# MCU.net
KiCad netlist of a schematic drawn in Altium Designer
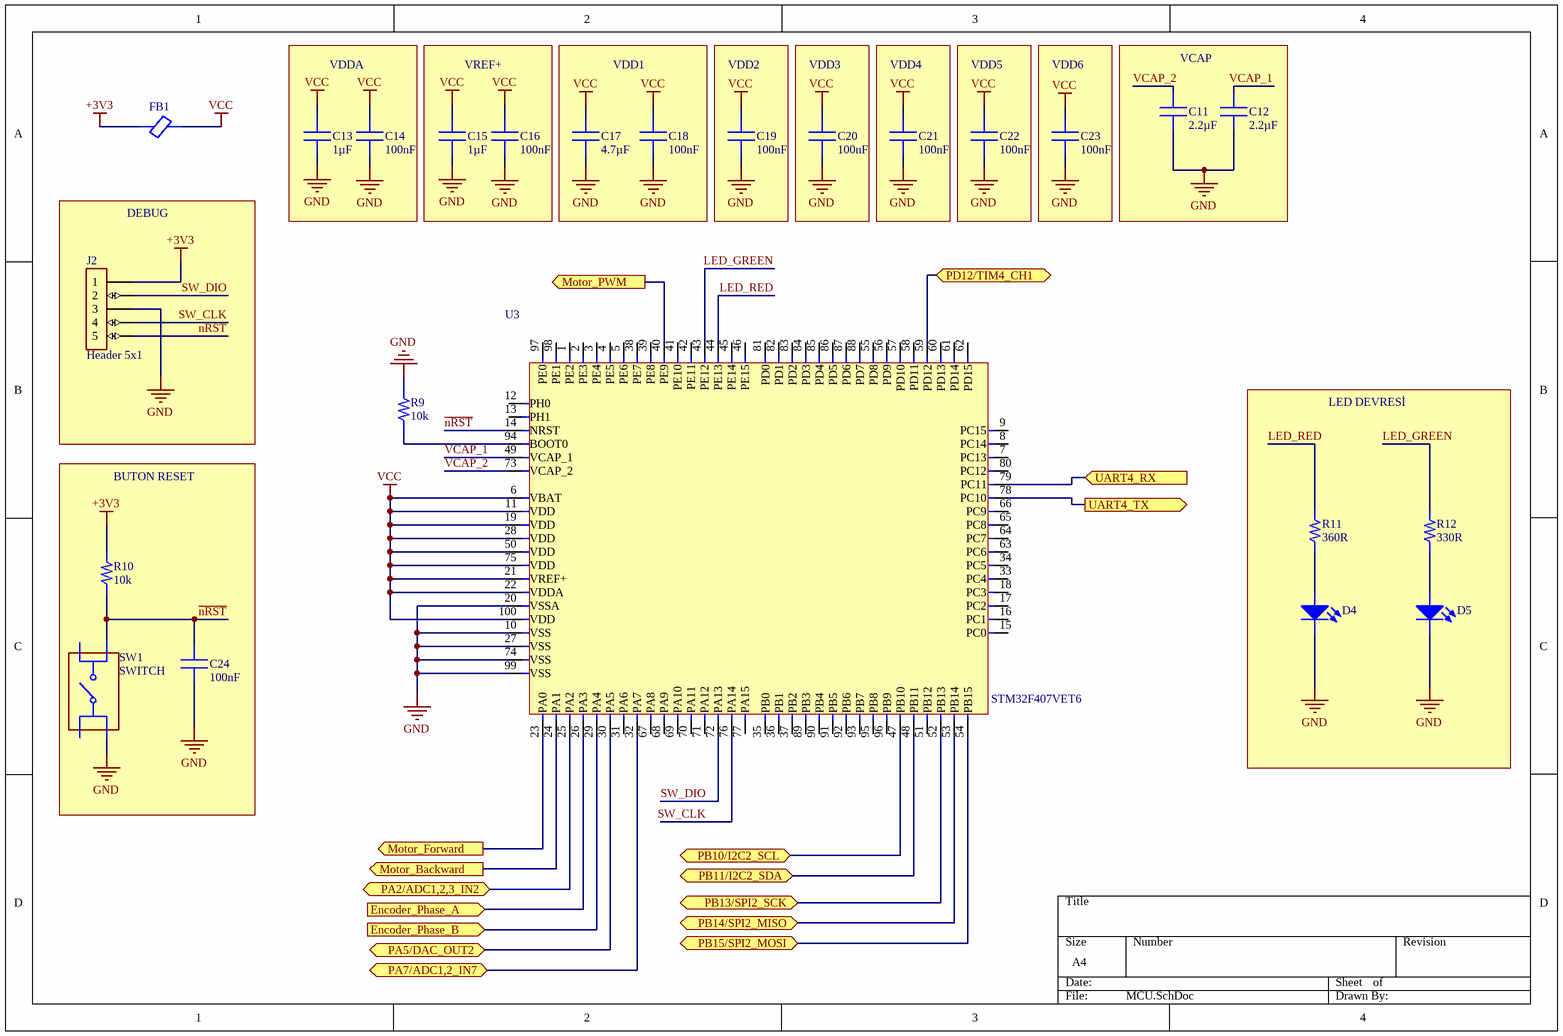
[diagram p0: MCU.SchDoc]

(export (version "E")
  (design (tool "Eeschema 10.0.6"))
  (components
    (comp (ref "C11")
      (value "2.2µF")
      (footprint "CAP 0402 2.2UF")
      (description "MLCC (1005) 0402 2.2uF 16VDC ±10% X5R CL05A225KO5NQNC")
      (fields (field (name "MANUFACTURER") "SAMSUNG") (field (name "TOLERANCE") "±10 %"))
      (libsource (lib "Motor Controller SchLib") (part "CAP 0402 2.2uF CL05A225KO5NQNC"))
    )
    (comp (ref "C12")
      (value "2.2µF")
      (footprint "CAP 0402 2.2UF")
      (description "MLCC (1005) 0402 2.2uF 16VDC ±10% X5R CL05A225KO5NQNC")
      (fields (field (name "MANUFACTURER") "SAMSUNG") (field (name "TOLERANCE") "±10 %"))
      (libsource (lib "Motor Controller SchLib") (part "CAP 0402 2.2uF CL05A225KO5NQNC"))
    )
    (comp (ref "C13")
      (value "1µF")
      (footprint "CAP 1uF 0402")
      (description "MLCC (1005) 0402 1uF 16VDC ±10% X5R CL05A105KO5NNNC")
      (fields (field (name "MANUFACTURER") "SAMSUNG") (field (name "TOLERANCE") "±10 %"))
      (libsource (lib "Motor Controller SchLib") (part "CAP 0402 1µF CL05A105KO5NNNC"))
    )
    (comp (ref "C14")
      (value "100nF")
      (footprint "CAP 100nF 0402")
      (description "MLCC (1005) 0402 100nF 16VDC ±10% X7R")
      (fields (field (name "TOLERANCE") "±10 %") (field (name "MANUFACTURER") "SAMSUNG"))
      (libsource (lib "Motor Controller SchLib") (part "CAP 0402 100nF"))
    )
    (comp (ref "C15")
      (value "1µF")
      (footprint "CAP 1uF 0402")
      (description "MLCC (1005) 0402 1uF 16VDC ±10% X5R CL05A105KO5NNNC")
      (fields (field (name "MANUFACTURER") "SAMSUNG") (field (name "TOLERANCE") "±10 %"))
      (libsource (lib "Motor Controller SchLib") (part "CAP 0402 1µF CL05A105KO5NNNC"))
    )
    (comp (ref "C16")
      (value "100nF")
      (footprint "CAP 100nF 0402")
      (description "MLCC (1005) 0402 100nF 16VDC ±10% X7R")
      (fields (field (name "TOLERANCE") "±10 %") (field (name "MANUFACTURER") "SAMSUNG"))
      (libsource (lib "Motor Controller SchLib") (part "CAP 0402 100nF"))
    )
    (comp (ref "C17")
      (value "4.7µF")
      (footprint "CAP 0402 4.7uF")
      (description "MLCC (1005) 0402 4.7uF 16VDC ±20% X5R CL05A475MO5LUNC")
      (fields (field (name "MANUFACTURER") "SAMSUNG") (field (name "TOLERANCE") "±20 %"))
      (libsource (lib "Motor Controller SchLib") (part "CAP 0402 4.7uF CL05A475MO5LUNC"))
    )
    (comp (ref "C18")
      (value "100nF")
      (footprint "CAP 100nF 0402")
      (description "MLCC (1005) 0402 100nF 16VDC ±10% X7R")
      (fields (field (name "TOLERANCE") "±10 %") (field (name "MANUFACTURER") "SAMSUNG"))
      (libsource (lib "Motor Controller SchLib") (part "CAP 0402 100nF"))
    )
    (comp (ref "C19")
      (value "100nF")
      (footprint "CAP 100nF 0402")
      (description "MLCC (1005) 0402 100nF 16VDC ±10% X7R")
      (fields (field (name "TOLERANCE") "±10 %") (field (name "MANUFACTURER") "SAMSUNG"))
      (libsource (lib "Motor Controller SchLib") (part "CAP 0402 100nF"))
    )
    (comp (ref "C20")
      (value "100nF")
      (footprint "CAP 100nF 0402")
      (description "MLCC (1005) 0402 100nF 16VDC ±10% X7R")
      (fields (field (name "TOLERANCE") "±10 %") (field (name "MANUFACTURER") "SAMSUNG"))
      (libsource (lib "Motor Controller SchLib") (part "CAP 0402 100nF"))
    )
    (comp (ref "C21")
      (value "100nF")
      (footprint "CAP 100nF 0402")
      (description "MLCC (1005) 0402 100nF 16VDC ±10% X7R")
      (fields (field (name "TOLERANCE") "±10 %") (field (name "MANUFACTURER") "SAMSUNG"))
      (libsource (lib "Motor Controller SchLib") (part "CAP 0402 100nF"))
    )
    (comp (ref "C22")
      (value "100nF")
      (footprint "CAP 100nF 0402")
      (description "MLCC (1005) 0402 100nF 16VDC ±10% X7R")
      (fields (field (name "TOLERANCE") "±10 %") (field (name "MANUFACTURER") "SAMSUNG"))
      (libsource (lib "Motor Controller SchLib") (part "CAP 0402 100nF"))
    )
    (comp (ref "C23")
      (value "100nF")
      (footprint "CAP 100nF 0402")
      (description "MLCC (1005) 0402 100nF 16VDC ±10% X7R")
      (fields (field (name "TOLERANCE") "±10 %") (field (name "MANUFACTURER") "SAMSUNG"))
      (libsource (lib "Motor Controller SchLib") (part "CAP 0402 100nF"))
    )
    (comp (ref "C24")
      (value "100nF")
      (footprint "CAP 100nF 0402")
      (description "MLCC (1005) 0402 100nF 16VDC ±10% X7R CL05B104KO5NNNC")
      (fields (field (name "TOLERANCE") "±10 %") (field (name "MANUFACTURER") "SAMSUNG"))
      (libsource (lib "Motor Controller SchLib") (part "CAP 0402 100nF CL05B104KO5NNNC"))
    )
    (comp (ref "D4")
      (value "LED RED")
      (footprint "LED RED 0603 APT1608EC")
      (description "LED SMD 0603 RED 617nm CLEAR CHIP SMD")
      (fields (field (name "MANUFACTURER") "KINGBRIGHT"))
      (libsource (lib "Motor Controller SchLib") (part "SMD LED RED APT1608EC"))
    )
    (comp (ref "D5")
      (value "LED GREEN")
      (footprint "LED GREEN 0603 APT1608CGCK")
      (description "LED GREEN CLEAR CHIP SMD")
      (fields (field (name "MANUFACTURER") "KINGBRIGHT"))
      (libsource (lib "Motor Controller SchLib") (part "SMD LED GREEN APT1608CGCK"))
    )
    (comp (ref "FB1")
      (value "BLM18PG221SN1D")
      (footprint "FB 0603 BLM18PG221SN1D")
      (description "FERRITE BEAD 0805 330R/100MHZ  BLM18PG221SN1D  SMD")
      (fields (field (name "MANUFACTURER") "MURATA") (field (name "TOLERANCE") "±25 %"))
      (libsource (lib "Motor Controller SchLib") (part "Ferrite Bead 330R/100MHz"))
    )
    (comp (ref "J2")
      (value "Header 5x1")
      (footprint "5x1 Header")
      (description "PIN HEADER 5PIN (5x1) 2.54mm THT V/T")
      (fields (field (name "MANUFACTURER") "CONNFLY"))
      (libsource (lib "Motor Controller SchLib") (part "Header 5x1 for SWD"))
    )
    (comp (ref "R9")
      (value "10k")
      (footprint "RES 0402 ROYALOHM GENERAL")
      (description "RES.(1005) 0402 10K Ohms 5% 1/16W 100PPM 0402WGJ0103TCE")
      (fields (field (name "TOLERANCE") "%5") (field (name "MANUFACTURER") "ROYALOHM"))
      (libsource (lib "Motor Controller SchLib") (part "RES 0402 10k"))
    )
    (comp (ref "R10")
      (value "10k")
      (footprint "RES 0402 ROYALOHM GENERAL")
      (description "RES.(1005) 0402 10K Ohms 5% 1/16W 100PPM 0402WGJ0103TCE")
      (fields (field (name "TOLERANCE") "%5") (field (name "MANUFACTURER") "ROYALOHM"))
      (libsource (lib "Motor Controller SchLib") (part "RES 0402 10k"))
    )
    (comp (ref "R11")
      (value "360R")
      (footprint "ROYALOHM 0603 RES")
      (description "RES.(1608) 0603 360 Ohms 5% 1/10W-S 100PPM 0603SAJ0361T5E")
      (fields (field (name "MANUFACTURER") "ROYALOHM") (field (name "TOLERANCE") "±5 %"))
      (libsource (lib "Motor Controller SchLib") (part "RES 0603 360R 0603SAJ0361T5E"))
    )
    (comp (ref "R12")
      (value "330R")
      (footprint "ROYALOHM 0603 RES")
      (description "RES 0603 330 Ohms 5% 1/10W-S 100PPM")
      (fields (field (name "TOLERANCE") "±5 %") (field (name "POWER") "1/10W"))
      (libsource (lib "Motor Controller SchLib") (part "RES 0603 330R"))
    )
    (comp (ref "SW1")
      (value "SWITCH")
      (footprint "PTS647SM50SMTR2 SMD BUTTON")
      (description "SWITCH TACT 6.00x6.00 8.00mm 160gF SMT V/T PTS647SM50SMTR2LFS")
      (fields (field (name "MANUFACTURER") "LITTELFUSE-C&K"))
      (libsource (lib "Motor Controller SchLib") (part "SMD BUTTON PTS647SM50SMTR2LFS"))
    )
    (comp (ref "U3")
      (value "STM32F407VET6")
      (footprint "LQFP100-0.5-13.8X13.8MM")
      (description "IC-32F407V MCU 32BIT 512KB FLASH 100LQFP")
      (fields (field (name "MANUFACTURER") "STM"))
      (libsource (lib "Motor Controller SchLib") (part "MCU-STM32F407VET6(LQFP100)"))
    )
  )
  (nets
    (net (code "1") (name "+3V3") (class "Default")
      (node (ref "FB1") (pin "1") (pinfunction "1_1") (pintype "passive"))
      (node (ref "J2") (pin "1") (pinfunction "1_1") (pintype "power_in"))
      (node (ref "R10") (pin "2") (pinfunction "2_2") (pintype "passive"))
    )
    (net (code "2") (name "/Encoder_Phase_A") (class "Default")
      (node (ref "U3") (pin "26") (pinfunction "PA3_26") (pintype "bidirectional"))
    )
    (net (code "3") (name "/Encoder_Phase_B") (class "Default")
      (node (ref "U3") (pin "29") (pinfunction "PA4_29") (pintype "bidirectional"))
    )
    (net (code "4") (name "/LED_GREEN") (class "Default")
      (node (ref "R12") (pin "2") (pinfunction "2_2") (pintype "passive"))
      (node (ref "U3") (pin "43") (pinfunction "PE12_43") (pintype "bidirectional"))
    )
    (net (code "5") (name "/LED_RED") (class "Default")
      (node (ref "R11") (pin "2") (pinfunction "2_2") (pintype "passive"))
      (node (ref "U3") (pin "44") (pinfunction "PE13_44") (pintype "bidirectional"))
    )
    (net (code "6") (name "/Motor_Backward") (class "Default")
      (node (ref "U3") (pin "24") (pinfunction "PA1_24") (pintype "bidirectional"))
    )
    (net (code "7") (name "/Motor_Forward") (class "Default")
      (node (ref "U3") (pin "23") (pinfunction "PA0_23") (pintype "bidirectional"))
    )
    (net (code "8") (name "/Motor_PWM") (class "Default")
      (node (ref "U3") (pin "40") (pinfunction "PE9_40") (pintype "bidirectional"))
    )
    (net (code "9") (name "/PA2{slash}ADC1,2,3_IN2") (class "Default")
      (node (ref "U3") (pin "25") (pinfunction "PA2_25") (pintype "bidirectional"))
    )
    (net (code "10") (name "/PA5{slash}DAC_OUT2") (class "Default")
      (node (ref "U3") (pin "30") (pinfunction "PA5_30") (pintype "bidirectional"))
    )
    (net (code "11") (name "/PA7{slash}ADC1,2_IN7") (class "Default")
      (node (ref "U3") (pin "32") (pinfunction "PA7_32") (pintype "bidirectional"))
    )
    (net (code "12") (name "/PB10{slash}I2C2_SCL") (class "Default")
      (node (ref "U3") (pin "47") (pinfunction "PB10_47") (pintype "bidirectional"))
    )
    (net (code "13") (name "/PB11{slash}I2C2_SDA") (class "Default")
      (node (ref "U3") (pin "48") (pinfunction "PB11_48") (pintype "bidirectional"))
    )
    (net (code "14") (name "/PB13{slash}SPI2_SCK") (class "Default")
      (node (ref "U3") (pin "52") (pinfunction "PB13_52") (pintype "bidirectional"))
    )
    (net (code "15") (name "/PB14{slash}SPI2_MISO") (class "Default")
      (node (ref "U3") (pin "53") (pinfunction "PB14_53") (pintype "bidirectional"))
    )
    (net (code "16") (name "/PB15{slash}SPI2_MOSI") (class "Default")
      (node (ref "U3") (pin "54") (pinfunction "PB15_54") (pintype "bidirectional"))
    )
    (net (code "17") (name "/PD12{slash}TIM4_CH1") (class "Default")
      (node (ref "U3") (pin "59") (pinfunction "PD12_59") (pintype "bidirectional"))
    )
    (net (code "18") (name "/SW_CLK") (class "Default")
      (node (ref "J2") (pin "4") (pinfunction "4_4") (pintype "bidirectional"))
      (node (ref "U3") (pin "76") (pinfunction "PA14_76") (pintype "bidirectional"))
    )
    (net (code "19") (name "/SW_DIO") (class "Default")
      (node (ref "J2") (pin "2") (pinfunction "2_2") (pintype "bidirectional"))
      (node (ref "U3") (pin "72") (pinfunction "PA13_72") (pintype "bidirectional"))
    )
    (net (code "20") (name "/UART4_RX") (class "Default")
      (node (ref "U3") (pin "79") (pinfunction "PC11_79") (pintype "bidirectional"))
    )
    (net (code "21") (name "/UART4_TX") (class "Default")
      (node (ref "U3") (pin "78") (pinfunction "PC10_78") (pintype "bidirectional"))
    )
    (net (code "22") (name "/VCAP_1") (class "Default")
      (node (ref "C12") (pin "2") (pinfunction "2_2") (pintype "passive"))
      (node (ref "U3") (pin "49") (pinfunction "VCAP_1_49") (pintype "bidirectional"))
    )
    (net (code "23") (name "/VCAP_2") (class "Default")
      (node (ref "C11") (pin "2") (pinfunction "2_2") (pintype "passive"))
      (node (ref "U3") (pin "73") (pinfunction "VCAP_2_73") (pintype "bidirectional"))
    )
    (net (code "24") (name "/~{nRST}") (class "Default")
      (node (ref "C24") (pin "2") (pinfunction "2_2") (pintype "passive"))
      (node (ref "J2") (pin "5") (pinfunction "5_5") (pintype "bidirectional"))
      (node (ref "R10") (pin "1") (pinfunction "1_1") (pintype "passive"))
      (node (ref "SW1") (pin "4") (pinfunction "B2_4") (pintype "passive"))
      (node (ref "U3") (pin "14") (pinfunction "NRST_14") (pintype "bidirectional"))
    )
    (net (code "25") (name "GND") (class "Default")
      (node (ref "C11") (pin "1") (pinfunction "1_1") (pintype "passive"))
      (node (ref "C12") (pin "1") (pinfunction "1_1") (pintype "passive"))
      (node (ref "C13") (pin "1") (pinfunction "1_1") (pintype "passive"))
      (node (ref "C14") (pin "1") (pinfunction "1_1") (pintype "passive"))
      (node (ref "C15") (pin "1") (pinfunction "1_1") (pintype "passive"))
      (node (ref "C16") (pin "1") (pinfunction "1_1") (pintype "passive"))
      (node (ref "C17") (pin "1") (pinfunction "1_1") (pintype "passive"))
      (node (ref "C18") (pin "1") (pinfunction "1_1") (pintype "passive"))
      (node (ref "C19") (pin "1") (pinfunction "1_1") (pintype "passive"))
      (node (ref "C20") (pin "1") (pinfunction "1_1") (pintype "passive"))
      (node (ref "C21") (pin "1") (pinfunction "1_1") (pintype "passive"))
      (node (ref "C22") (pin "1") (pinfunction "1_1") (pintype "passive"))
      (node (ref "C23") (pin "1") (pinfunction "1_1") (pintype "passive"))
      (node (ref "C24") (pin "1") (pinfunction "1_1") (pintype "passive"))
      (node (ref "D4") (pin "C") (pinfunction "Cathode_C") (pintype "passive"))
      (node (ref "D5") (pin "C") (pinfunction "Cathode_C") (pintype "passive"))
      (node (ref "J2") (pin "3") (pinfunction "3_3") (pintype "power_in"))
      (node (ref "R9") (pin "2") (pinfunction "2_2") (pintype "passive"))
      (node (ref "SW1") (pin "2") (pinfunction "A2_2") (pintype "passive"))
      (node (ref "U3") (pin "10") (pinfunction "VSS_10") (pintype "bidirectional"))
      (node (ref "U3") (pin "20") (pinfunction "VSSA_20") (pintype "bidirectional"))
      (node (ref "U3") (pin "27") (pinfunction "VSS_27") (pintype "bidirectional"))
      (node (ref "U3") (pin "74") (pinfunction "VSS_74") (pintype "bidirectional"))
      (node (ref "U3") (pin "99") (pinfunction "VSS_99") (pintype "bidirectional"))
    )
    (net (code "26") (name "Net-(D4-Anode)") (class "Default")
      (node (ref "D4") (pin "A") (pinfunction "Anode_A") (pintype "passive"))
      (node (ref "R11") (pin "1") (pinfunction "1_1") (pintype "passive"))
    )
    (net (code "27") (name "Net-(D5-Anode)") (class "Default")
      (node (ref "D5") (pin "A") (pinfunction "Anode_A") (pintype "passive"))
      (node (ref "R12") (pin "1") (pinfunction "1_1") (pintype "passive"))
    )
    (net (code "28") (name "Net-(U3-BOOT0)") (class "Default")
      (node (ref "R9") (pin "1") (pinfunction "1_1") (pintype "passive"))
      (node (ref "U3") (pin "94") (pinfunction "BOOT0_94") (pintype "bidirectional"))
    )
    (net (code "29") (name "VCC") (class "Default")
      (node (ref "C13") (pin "2") (pinfunction "2_2") (pintype "passive"))
      (node (ref "C14") (pin "2") (pinfunction "2_2") (pintype "passive"))
      (node (ref "C15") (pin "2") (pinfunction "2_2") (pintype "passive"))
      (node (ref "C16") (pin "2") (pinfunction "2_2") (pintype "passive"))
      (node (ref "C17") (pin "2") (pinfunction "2_2") (pintype "passive"))
      (node (ref "C18") (pin "2") (pinfunction "2_2") (pintype "passive"))
      (node (ref "C19") (pin "2") (pinfunction "2_2") (pintype "passive"))
      (node (ref "C20") (pin "2") (pinfunction "2_2") (pintype "passive"))
      (node (ref "C21") (pin "2") (pinfunction "2_2") (pintype "passive"))
      (node (ref "C22") (pin "2") (pinfunction "2_2") (pintype "passive"))
      (node (ref "C23") (pin "2") (pinfunction "2_2") (pintype "passive"))
      (node (ref "FB1") (pin "2") (pinfunction "2_2") (pintype "passive"))
      (node (ref "U3") (pin "100") (pinfunction "VDD_100") (pintype "bidirectional"))
      (node (ref "U3") (pin "11") (pinfunction "VDD_11") (pintype "bidirectional"))
      (node (ref "U3") (pin "19") (pinfunction "VDD_19") (pintype "bidirectional"))
      (node (ref "U3") (pin "21") (pinfunction "VREF+_21") (pintype "bidirectional"))
      (node (ref "U3") (pin "22") (pinfunction "VDDA_22") (pintype "bidirectional"))
      (node (ref "U3") (pin "28") (pinfunction "VDD_28") (pintype "bidirectional"))
      (node (ref "U3") (pin "50") (pinfunction "VDD_50") (pintype "bidirectional"))
      (node (ref "U3") (pin "6") (pinfunction "VBAT_6") (pintype "bidirectional"))
      (node (ref "U3") (pin "75") (pinfunction "VDD_75") (pintype "bidirectional"))
    )
    (net (code "30") (name "unconnected-(SW1-A1-Pad1)") (class "Default")
      (node (ref "SW1") (pin "1") (pinfunction "A1_1") (pintype "passive"))
    )
    (net (code "31") (name "unconnected-(SW1-B1-Pad3)") (class "Default")
      (node (ref "SW1") (pin "3") (pinfunction "B1_3") (pintype "passive"))
    )
    (net (code "32") (name "unconnected-(U3-PA6-Pad31)") (class "Default")
      (node (ref "U3") (pin "31") (pinfunction "PA6_31") (pintype "bidirectional"))
    )
    (net (code "33") (name "unconnected-(U3-PA8-Pad67)") (class "Default")
      (node (ref "U3") (pin "67") (pinfunction "PA8_67") (pintype "bidirectional"))
    )
    (net (code "34") (name "unconnected-(U3-PA9-Pad68)") (class "Default")
      (node (ref "U3") (pin "68") (pinfunction "PA9_68") (pintype "bidirectional"))
    )
    (net (code "35") (name "unconnected-(U3-PA10-Pad69)") (class "Default")
      (node (ref "U3") (pin "69") (pinfunction "PA10_69") (pintype "bidirectional"))
    )
    (net (code "36") (name "unconnected-(U3-PA11-Pad70)") (class "Default")
      (node (ref "U3") (pin "70") (pinfunction "PA11_70") (pintype "bidirectional"))
    )
    (net (code "37") (name "unconnected-(U3-PA12-Pad71)") (class "Default")
      (node (ref "U3") (pin "71") (pinfunction "PA12_71") (pintype "bidirectional"))
    )
    (net (code "38") (name "unconnected-(U3-PA15-Pad77)") (class "Default")
      (node (ref "U3") (pin "77") (pinfunction "PA15_77") (pintype "bidirectional"))
    )
    (net (code "39") (name "unconnected-(U3-PB0-Pad35)") (class "Default")
      (node (ref "U3") (pin "35") (pinfunction "PB0_35") (pintype "bidirectional"))
    )
    (net (code "40") (name "unconnected-(U3-PB1-Pad36)") (class "Default")
      (node (ref "U3") (pin "36") (pinfunction "PB1_36") (pintype "bidirectional"))
    )
    (net (code "41") (name "unconnected-(U3-PB2-Pad37)") (class "Default")
      (node (ref "U3") (pin "37") (pinfunction "PB2_37") (pintype "bidirectional"))
    )
    (net (code "42") (name "unconnected-(U3-PB3-Pad89)") (class "Default")
      (node (ref "U3") (pin "89") (pinfunction "PB3_89") (pintype "bidirectional"))
    )
    (net (code "43") (name "unconnected-(U3-PB4-Pad90)") (class "Default")
      (node (ref "U3") (pin "90") (pinfunction "PB4_90") (pintype "bidirectional"))
    )
    (net (code "44") (name "unconnected-(U3-PB5-Pad91)") (class "Default")
      (node (ref "U3") (pin "91") (pinfunction "PB5_91") (pintype "bidirectional"))
    )
    (net (code "45") (name "unconnected-(U3-PB6-Pad92)") (class "Default")
      (node (ref "U3") (pin "92") (pinfunction "PB6_92") (pintype "bidirectional"))
    )
    (net (code "46") (name "unconnected-(U3-PB7-Pad93)") (class "Default")
      (node (ref "U3") (pin "93") (pinfunction "PB7_93") (pintype "bidirectional"))
    )
    (net (code "47") (name "unconnected-(U3-PB8-Pad95)") (class "Default")
      (node (ref "U3") (pin "95") (pinfunction "PB8_95") (pintype "bidirectional"))
    )
    (net (code "48") (name "unconnected-(U3-PB9-Pad96)") (class "Default")
      (node (ref "U3") (pin "96") (pinfunction "PB9_96") (pintype "bidirectional"))
    )
    (net (code "49") (name "unconnected-(U3-PB12-Pad51)") (class "Default")
      (node (ref "U3") (pin "51") (pinfunction "PB12_51") (pintype "bidirectional"))
    )
    (net (code "50") (name "unconnected-(U3-PC0-Pad15)") (class "Default")
      (node (ref "U3") (pin "15") (pinfunction "PC0_15") (pintype "bidirectional"))
    )
    (net (code "51") (name "unconnected-(U3-PC1-Pad16)") (class "Default")
      (node (ref "U3") (pin "16") (pinfunction "PC1_16") (pintype "bidirectional"))
    )
    (net (code "52") (name "unconnected-(U3-PC2-Pad17)") (class "Default")
      (node (ref "U3") (pin "17") (pinfunction "PC2_17") (pintype "bidirectional"))
    )
    (net (code "53") (name "unconnected-(U3-PC3-Pad18)") (class "Default")
      (node (ref "U3") (pin "18") (pinfunction "PC3_18") (pintype "bidirectional"))
    )
    (net (code "54") (name "unconnected-(U3-PC4-Pad33)") (class "Default")
      (node (ref "U3") (pin "33") (pinfunction "PC4_33") (pintype "bidirectional"))
    )
    (net (code "55") (name "unconnected-(U3-PC5-Pad34)") (class "Default")
      (node (ref "U3") (pin "34") (pinfunction "PC5_34") (pintype "bidirectional"))
    )
    (net (code "56") (name "unconnected-(U3-PC6-Pad63)") (class "Default")
      (node (ref "U3") (pin "63") (pinfunction "PC6_63") (pintype "bidirectional"))
    )
    (net (code "57") (name "unconnected-(U3-PC7-Pad64)") (class "Default")
      (node (ref "U3") (pin "64") (pinfunction "PC7_64") (pintype "bidirectional"))
    )
    (net (code "58") (name "unconnected-(U3-PC8-Pad65)") (class "Default")
      (node (ref "U3") (pin "65") (pinfunction "PC8_65") (pintype "bidirectional"))
    )
    (net (code "59") (name "unconnected-(U3-PC9-Pad66)") (class "Default")
      (node (ref "U3") (pin "66") (pinfunction "PC9_66") (pintype "bidirectional"))
    )
    (net (code "60") (name "unconnected-(U3-PC12-Pad80)") (class "Default")
      (node (ref "U3") (pin "80") (pinfunction "PC12_80") (pintype "bidirectional"))
    )
    (net (code "61") (name "unconnected-(U3-PC13-Pad7)") (class "Default")
      (node (ref "U3") (pin "7") (pinfunction "PC13_7") (pintype "bidirectional"))
    )
    (net (code "62") (name "unconnected-(U3-PC14-Pad8)") (class "Default")
      (node (ref "U3") (pin "8") (pinfunction "PC14_8") (pintype "bidirectional"))
    )
    (net (code "63") (name "unconnected-(U3-PC15-Pad9)") (class "Default")
      (node (ref "U3") (pin "9") (pinfunction "PC15_9") (pintype "bidirectional"))
    )
    (net (code "64") (name "unconnected-(U3-PD0-Pad81)") (class "Default")
      (node (ref "U3") (pin "81") (pinfunction "PD0_81") (pintype "bidirectional"))
    )
    (net (code "65") (name "unconnected-(U3-PD1-Pad82)") (class "Default")
      (node (ref "U3") (pin "82") (pinfunction "PD1_82") (pintype "bidirectional"))
    )
    (net (code "66") (name "unconnected-(U3-PD2-Pad83)") (class "Default")
      (node (ref "U3") (pin "83") (pinfunction "PD2_83") (pintype "bidirectional"))
    )
    (net (code "67") (name "unconnected-(U3-PD3-Pad84)") (class "Default")
      (node (ref "U3") (pin "84") (pinfunction "PD3_84") (pintype "bidirectional"))
    )
    (net (code "68") (name "unconnected-(U3-PD4-Pad85)") (class "Default")
      (node (ref "U3") (pin "85") (pinfunction "PD4_85") (pintype "bidirectional"))
    )
    (net (code "69") (name "unconnected-(U3-PD5-Pad86)") (class "Default")
      (node (ref "U3") (pin "86") (pinfunction "PD5_86") (pintype "bidirectional"))
    )
    (net (code "70") (name "unconnected-(U3-PD6-Pad87)") (class "Default")
      (node (ref "U3") (pin "87") (pinfunction "PD6_87") (pintype "bidirectional"))
    )
    (net (code "71") (name "unconnected-(U3-PD7-Pad88)") (class "Default")
      (node (ref "U3") (pin "88") (pinfunction "PD7_88") (pintype "bidirectional"))
    )
    (net (code "72") (name "unconnected-(U3-PD8-Pad55)") (class "Default")
      (node (ref "U3") (pin "55") (pinfunction "PD8_55") (pintype "bidirectional"))
    )
    (net (code "73") (name "unconnected-(U3-PD9-Pad56)") (class "Default")
      (node (ref "U3") (pin "56") (pinfunction "PD9_56") (pintype "bidirectional"))
    )
    (net (code "74") (name "unconnected-(U3-PD10-Pad57)") (class "Default")
      (node (ref "U3") (pin "57") (pinfunction "PD10_57") (pintype "bidirectional"))
    )
    (net (code "75") (name "unconnected-(U3-PD11-Pad58)") (class "Default")
      (node (ref "U3") (pin "58") (pinfunction "PD11_58") (pintype "bidirectional"))
    )
    (net (code "76") (name "unconnected-(U3-PD13-Pad60)") (class "Default")
      (node (ref "U3") (pin "60") (pinfunction "PD13_60") (pintype "bidirectional"))
    )
    (net (code "77") (name "unconnected-(U3-PD14-Pad61)") (class "Default")
      (node (ref "U3") (pin "61") (pinfunction "PD14_61") (pintype "bidirectional"))
    )
    (net (code "78") (name "unconnected-(U3-PD15-Pad62)") (class "Default")
      (node (ref "U3") (pin "62") (pinfunction "PD15_62") (pintype "bidirectional"))
    )
    (net (code "79") (name "unconnected-(U3-PE0-Pad97)") (class "Default")
      (node (ref "U3") (pin "97") (pinfunction "PE0_97") (pintype "bidirectional"))
    )
    (net (code "80") (name "unconnected-(U3-PE1-Pad98)") (class "Default")
      (node (ref "U3") (pin "98") (pinfunction "PE1_98") (pintype "bidirectional"))
    )
    (net (code "81") (name "unconnected-(U3-PE2-Pad1)") (class "Default")
      (node (ref "U3") (pin "1") (pinfunction "PE2_1") (pintype "bidirectional"))
    )
    (net (code "82") (name "unconnected-(U3-PE3-Pad2)") (class "Default")
      (node (ref "U3") (pin "2") (pinfunction "PE3_2") (pintype "bidirectional"))
    )
    (net (code "83") (name "unconnected-(U3-PE4-Pad3)") (class "Default")
      (node (ref "U3") (pin "3") (pinfunction "PE4_3") (pintype "bidirectional"))
    )
    (net (code "84") (name "unconnected-(U3-PE5-Pad4)") (class "Default")
      (node (ref "U3") (pin "4") (pinfunction "PE5_4") (pintype "bidirectional"))
    )
    (net (code "85") (name "unconnected-(U3-PE6-Pad5)") (class "Default")
      (node (ref "U3") (pin "5") (pinfunction "PE6_5") (pintype "bidirectional"))
    )
    (net (code "86") (name "unconnected-(U3-PE7-Pad38)") (class "Default")
      (node (ref "U3") (pin "38") (pinfunction "PE7_38") (pintype "bidirectional"))
    )
    (net (code "87") (name "unconnected-(U3-PE8-Pad39)") (class "Default")
      (node (ref "U3") (pin "39") (pinfunction "PE8_39") (pintype "bidirectional"))
    )
    (net (code "88") (name "unconnected-(U3-PE10-Pad41)") (class "Default")
      (node (ref "U3") (pin "41") (pinfunction "PE10_41") (pintype "bidirectional"))
    )
    (net (code "89") (name "unconnected-(U3-PE11-Pad42)") (class "Default")
      (node (ref "U3") (pin "42") (pinfunction "PE11_42") (pintype "bidirectional"))
    )
    (net (code "90") (name "unconnected-(U3-PE14-Pad45)") (class "Default")
      (node (ref "U3") (pin "45") (pinfunction "PE14_45") (pintype "bidirectional"))
    )
    (net (code "91") (name "unconnected-(U3-PE15-Pad46)") (class "Default")
      (node (ref "U3") (pin "46") (pinfunction "PE15_46") (pintype "bidirectional"))
    )
    (net (code "92") (name "unconnected-(U3-PH0-Pad12)") (class "Default")
      (node (ref "U3") (pin "12") (pinfunction "PH0_12") (pintype "bidirectional"))
    )
    (net (code "93") (name "unconnected-(U3-PH1-Pad13)") (class "Default")
      (node (ref "U3") (pin "13") (pinfunction "PH1_13") (pintype "bidirectional"))
    )
  )
)
